# Battery_Circuit.net
KiCad netlist of a schematic drawn in Altium Designer
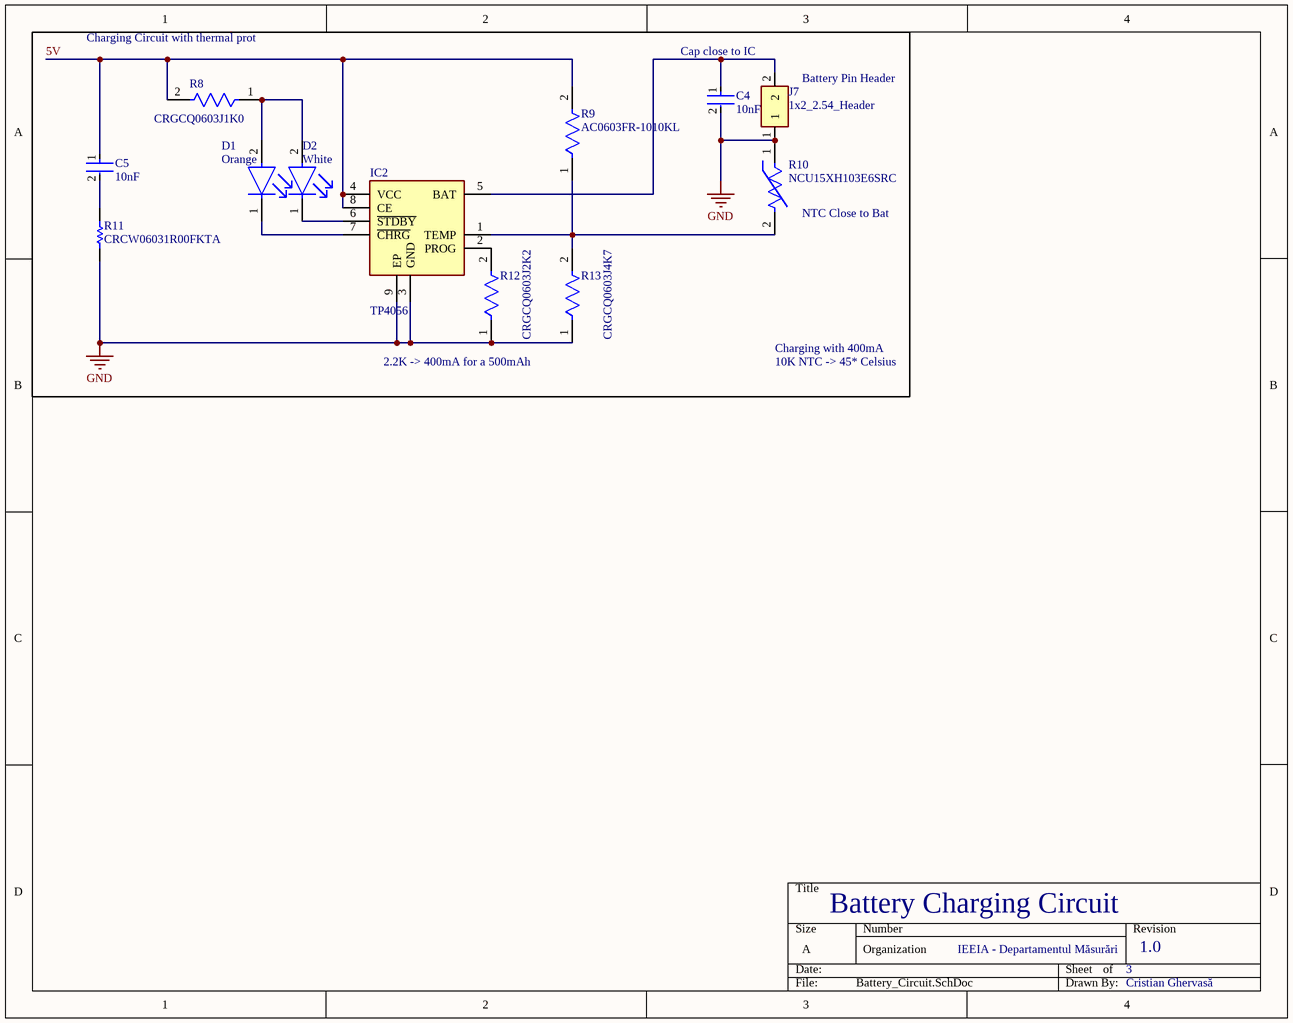
[diagram p0: Battery_Circuit.SchDoc]

(export (version "E")
  (design (tool "Eeschema 10.0.6"))
  (components
    (comp (ref "C4")
      (value "10nF")
      (footprint "FP-CL10-IPC_C")
      (description "Cap Ceramic 10nF 25V X7R ±10% Pad SMD 0603 +125°C T/R")
      (fields (field (name "TOLERANCE") "10%") (field (name "VOLTAGE") "50V"))
      (libsource (lib "Altium Content Vault") (part "b4654b650e69147ec39a6b967a45e02"))
    )
    (comp (ref "C5")
      (value "10nF")
      (footprint "FP-CL10-IPC_C")
      (description "Cap Ceramic 10nF 25V X7R ±10% Pad SMD 0603 +125°C T/R")
      (fields (field (name "TOLERANCE") "10%") (field (name "VOLTAGE") "50V"))
      (libsource (lib "Altium Content Vault") (part "b4654b650e69147ec39a6b967a45e02"))
    )
    (comp (ref "D1")
      (value "Orange")
      (footprint "FP-LTST-C190KFKT-MFG")
      (description "LED ORANGE CLEAR CHIP SMD")
      (libsource (lib "Altium Content Vault") (part "8706943c75ba83719d021d2fdc84c58"))
    )
    (comp (ref "D2")
      (value "White")
      (footprint "FP-6_541-5091_01-4-MFG")
      (description "LED COOL WHITE 0603 SMD")
      (fields
        (field (name "MANUFACTURER") "Vishay")
        (field (name "MANUFACTURER PART NUMBER") "VLMW1300-GS08")
      )
      (libsource (lib "Altium Content Vault") (part "8706943c75ba83719d021d2fdc84c58"))
    )
    (comp (ref "IC2")
      (value "TP4056")
      (footprint "SamacSys:SOIC127P600X175-9N")
      (description "Integrated Circuit")
      (libsource (lib "SamacSys") (part "TP4056"))
    )
    (comp (ref "J7")
      (value "1x2_2.54_Header")
      (footprint "1x2_2.54_Header")
      (description "Connector")
      (libsource (lib "NFC_MedicalAQ") (part "1x2_2.54_Header"))
    )
    (comp (ref "R8")
      (value "CRGCQ0603J1K0")
      (footprint "FP-CRGCQ0603-IPC_C")
      (description "CRGCQ 0603 1K0 5%")
      (fields (field (name "MANUFACTURER") "TE Connectivity") (field (name "TOLERANCE") "0.05"))
      (libsource (lib "Altium Content Vault") (part "1029c3af85768c4190bb7ad29bc67b5"))
    )
    (comp (ref "R9")
      (value "AC0603FR-1010KL")
      (footprint "FP-AC0603-IPC_B")
      (description "RES 10KΩ 1.00% 0.1W 0603")
      (fields (field (name "TOLERANCE") "1%"))
      (libsource (lib "Altium Content Vault") (part "1029c3af85768c4190bb7ad29bc67b5"))
    )
    (comp (ref "R10")
      (value "NCU15XH103E6SRC")
      (footprint "FP-NCP15-NCU15-0_05-IPC_A")
      (description "NTC Thermistor for Temperature Sensor, Automotive, 0402, 10kΩ, 3%, 0.1mA, 5V")
      (libsource (lib "Altium Content Vault") (part "3b148a6ebabc5fb4d708a66c052d352"))
    )
    (comp (ref "R11")
      (value "CRCW06031R00FKTA")
      (footprint "RESC1609X50X30NL10T20")
      (description "1OHM")
      (fields (field (name "MANUFACTURER") "Vishay Dale"))
      (libsource (lib "Altium Content Vault") (part "RES"))
    )
    (comp (ref "R12")
      (value "CRGCQ0603J2K2")
      (footprint "FP-CRGCQ0603-IPC_C")
      (description "CRGCQ0603 2.2KΩ 5% ±100ppm/°C 75V")
      (fields
        (field (name "TOLERANCE") "0.05")
        (field (name "OCTOPART") "https://octopart.com/crgcq0603j2k2-te+connectivity-91018114")
      )
      (libsource (lib "Altium Content Vault") (part "1029c3af85768c4190bb7ad29bc67b5"))
    )
    (comp (ref "R13")
      (value "CRGCQ0603J4K7")
      (footprint "FP-CRGCQ0603-IPC_C")
      (description "CRGCQ 0603 4K7 5%")
      (fields
        (field (name "TOLERANCE") "0.05")
        (field (name "OCTOPART") "https://octopart.com/crgcq0603j4k7-te+connectivity-91018128")
      )
      (libsource (lib "Altium Content Vault") (part "1029c3af85768c4190bb7ad29bc67b5"))
    )
  )
  (nets
    (net (code "1") (name "/5V") (class "Default")
      (node (ref "C5") (pin "1") (pinfunction "1_1") (pintype "passive"))
      (node (ref "IC2") (pin "4") (pinfunction "VCC_4") (pintype "passive"))
      (node (ref "IC2") (pin "8") (pinfunction "CE_8") (pintype "passive"))
      (node (ref "R8") (pin "2") (pinfunction "2_2") (pintype "passive"))
      (node (ref "R9") (pin "2") (pinfunction "2_2") (pintype "passive"))
    )
    (net (code "2") (name "GND") (class "Default")
      (node (ref "C4") (pin "2") (pinfunction "2_2") (pintype "passive"))
      (node (ref "IC2") (pin "3") (pinfunction "GND_3") (pintype "passive"))
      (node (ref "IC2") (pin "9") (pinfunction "EP_9") (pintype "passive"))
      (node (ref "J7") (pin "1") (pinfunction "1_1") (pintype "passive"))
      (node (ref "R10") (pin "1") (pinfunction "1_1") (pintype "passive"))
      (node (ref "R11") (pin "1") (pinfunction "1_1") (pintype "passive"))
      (node (ref "R12") (pin "1") (pinfunction "1_1") (pintype "passive"))
      (node (ref "R13") (pin "1") (pinfunction "1_1") (pintype "passive"))
    )
    (net (code "3") (name "Net-(C5-Pad2)") (class "Default")
      (node (ref "C5") (pin "2") (pinfunction "2_2") (pintype "passive"))
      (node (ref "R11") (pin "2") (pinfunction "2_2") (pintype "passive"))
    )
    (net (code "4") (name "Net-(D1-A)") (class "Default")
      (node (ref "D1") (pin "2") (pinfunction "A_2") (pintype "passive"))
      (node (ref "D2") (pin "2") (pinfunction "A_2") (pintype "passive"))
      (node (ref "R8") (pin "1") (pinfunction "1_1") (pintype "passive"))
    )
    (net (code "5") (name "Net-(D1-C)") (class "Default")
      (node (ref "D1") (pin "1") (pinfunction "C_1") (pintype "passive"))
      (node (ref "IC2") (pin "7") (pinfunction "~{CHRG}_7") (pintype "passive"))
    )
    (net (code "6") (name "Net-(D2-C)") (class "Default")
      (node (ref "D2") (pin "1") (pinfunction "C_1") (pintype "passive"))
      (node (ref "IC2") (pin "6") (pinfunction "~{STDBY}_6") (pintype "passive"))
    )
    (net (code "7") (name "Net-(IC2-BAT)") (class "Default")
      (node (ref "C4") (pin "1") (pinfunction "1_1") (pintype "passive"))
      (node (ref "IC2") (pin "5") (pinfunction "BAT_5") (pintype "passive"))
      (node (ref "J7") (pin "2") (pinfunction "2_2") (pintype "passive"))
    )
    (net (code "8") (name "Net-(IC2-PROG)") (class "Default")
      (node (ref "IC2") (pin "2") (pinfunction "PROG_2") (pintype "passive"))
      (node (ref "R12") (pin "2") (pinfunction "2_2") (pintype "passive"))
    )
    (net (code "9") (name "Net-(IC2-TEMP)") (class "Default")
      (node (ref "IC2") (pin "1") (pinfunction "TEMP_1") (pintype "passive"))
      (node (ref "R10") (pin "2") (pinfunction "2_2") (pintype "passive"))
      (node (ref "R13") (pin "2") (pinfunction "2_2") (pintype "passive"))
      (node (ref "R9") (pin "1") (pinfunction "1_1") (pintype "passive"))
    )
  )
)
